# ESP_LED_CUBE.net
KiCad netlist of a schematic drawn in EAGLE
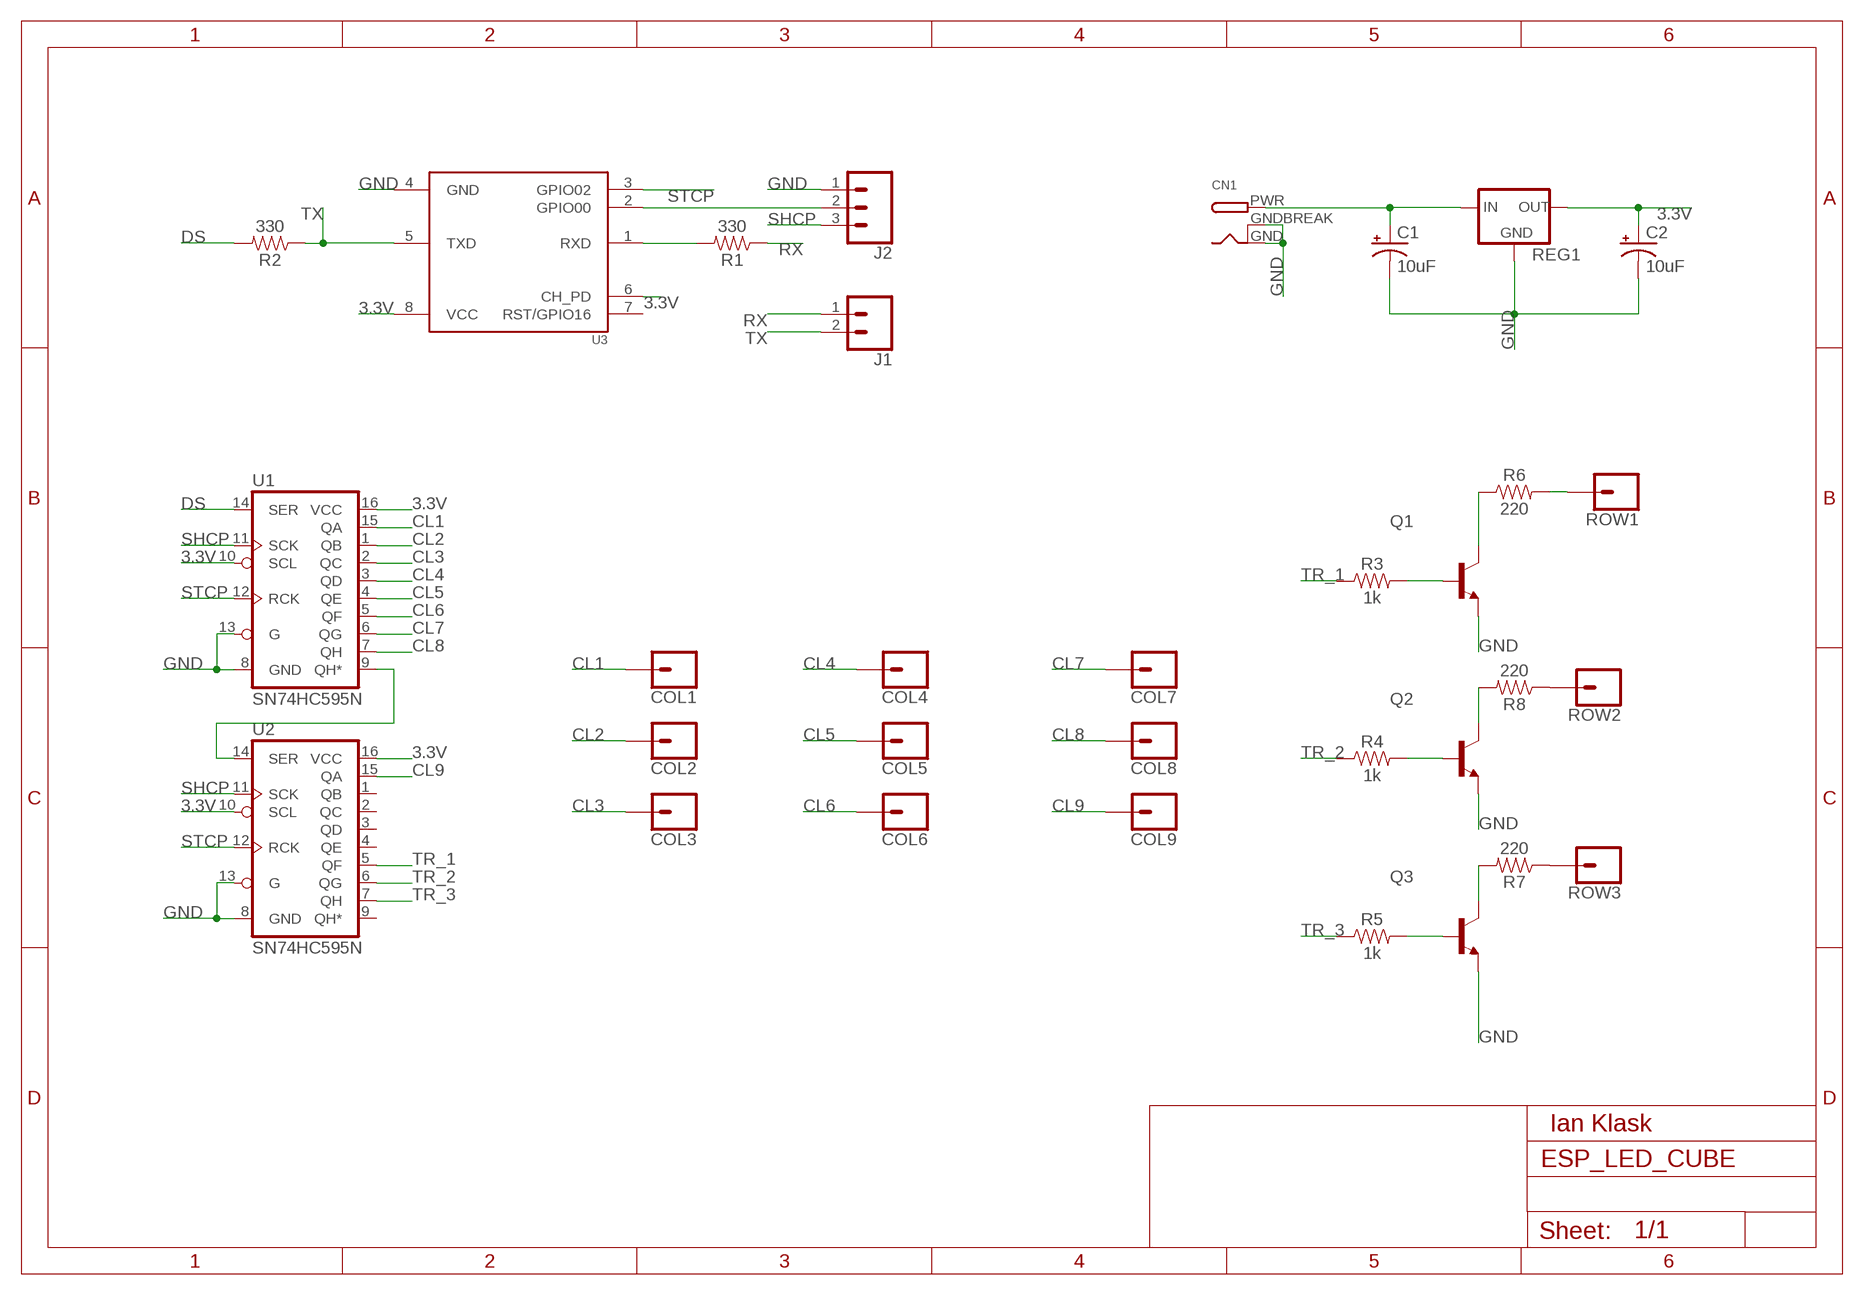
[diagram p0: schematic, sheet 1]

(export (version "E")
  (design (tool "Eeschema 10.0.6"))
  (components
    (comp (ref "C1")
      (value "10uF")
      (footprint "eagle-import:CPOL-RADIAL-2.5MM-5MM")
      (libsource (lib "eagle-import") (part "10UF-POLAR-RADIAL-2.5MM-25V-20%"))
    )
    (comp (ref "C2")
      (value "10uF")
      (footprint "eagle-import:CPOL-RADIAL-2.5MM-5MM")
      (libsource (lib "eagle-import") (part "10UF-POLAR-RADIAL-2.5MM-25V-20%"))
    )
    (comp (ref "CN1")
      (value "DCBARRELPTH")
      (footprint "eagle-import:DCJACK_2MM_PTH")
      (libsource (lib "eagle-import") (part "DCBARRELPTH"))
    )
    (comp (ref "COL1")
      (value "CONN_01")
      (footprint "eagle-import:1X01")
      (libsource (lib "eagle-import") (part "CONN_01"))
    )
    (comp (ref "COL2")
      (value "CONN_01")
      (footprint "eagle-import:1X01")
      (libsource (lib "eagle-import") (part "CONN_01"))
    )
    (comp (ref "COL3")
      (value "CONN_01")
      (footprint "eagle-import:1X01")
      (libsource (lib "eagle-import") (part "CONN_01"))
    )
    (comp (ref "COL4")
      (value "CONN_01")
      (footprint "eagle-import:1X01")
      (libsource (lib "eagle-import") (part "CONN_01"))
    )
    (comp (ref "COL5")
      (value "CONN_01")
      (footprint "eagle-import:1X01")
      (libsource (lib "eagle-import") (part "CONN_01"))
    )
    (comp (ref "COL6")
      (value "CONN_01")
      (footprint "eagle-import:1X01")
      (libsource (lib "eagle-import") (part "CONN_01"))
    )
    (comp (ref "COL7")
      (value "CONN_01")
      (footprint "eagle-import:1X01")
      (libsource (lib "eagle-import") (part "CONN_01"))
    )
    (comp (ref "COL8")
      (value "CONN_01")
      (footprint "eagle-import:1X01")
      (libsource (lib "eagle-import") (part "CONN_01"))
    )
    (comp (ref "COL9")
      (value "CONN_01")
      (footprint "eagle-import:1X01")
      (libsource (lib "eagle-import") (part "CONN_01"))
    )
    (comp (ref "J1")
      (value "CONN_02")
      (footprint "eagle-import:1X02")
      (libsource (lib "eagle-import") (part "CONN_02"))
    )
    (comp (ref "J2")
      (value "CONN_03")
      (footprint "eagle-import:1X03")
      (libsource (lib "eagle-import") (part "CONN_03"))
    )
    (comp (ref "Q1")
      (value "2N3904")
      (footprint "eagle-import:TO92")
      (libsource (lib "eagle-import") (part "2N3904"))
    )
    (comp (ref "Q2")
      (value "2N3904")
      (footprint "eagle-import:TO92")
      (libsource (lib "eagle-import") (part "2N3904"))
    )
    (comp (ref "Q3")
      (value "2N3904")
      (footprint "eagle-import:TO92")
      (libsource (lib "eagle-import") (part "2N3904"))
    )
    (comp (ref "R1")
      (value "330")
      (footprint "eagle-import:AXIAL-0.3")
      (libsource (lib "eagle-import") (part "330OHM-HORIZ-1/10W-5%"))
    )
    (comp (ref "R2")
      (value "330")
      (footprint "eagle-import:AXIAL-0.3")
      (libsource (lib "eagle-import") (part "330OHM-HORIZ-1/10W-5%"))
    )
    (comp (ref "R3")
      (value "1k")
      (footprint "eagle-import:AXIAL-0.3")
      (libsource (lib "eagle-import") (part "1KOHM-HORIZ-1/4W-1%"))
    )
    (comp (ref "R4")
      (value "1k")
      (footprint "eagle-import:AXIAL-0.3")
      (libsource (lib "eagle-import") (part "1KOHM-HORIZ-1/4W-1%"))
    )
    (comp (ref "R5")
      (value "1k")
      (footprint "eagle-import:AXIAL-0.3")
      (libsource (lib "eagle-import") (part "1KOHM-HORIZ-1/4W-1%"))
    )
    (comp (ref "R6")
      (value "220")
      (footprint "eagle-import:AXIAL-0.3")
      (libsource (lib "eagle-import") (part "330OHM-HORIZ-1/10W-5%"))
    )
    (comp (ref "R7")
      (value "220")
      (footprint "eagle-import:AXIAL-0.3")
      (libsource (lib "eagle-import") (part "330OHM-HORIZ-1/10W-5%"))
    )
    (comp (ref "R8")
      (value "220")
      (footprint "eagle-import:AXIAL-0.3")
      (libsource (lib "eagle-import") (part "330OHM-HORIZ-1/10W-5%"))
    )
    (comp (ref "REG1")
      (value "V_REG_LD1117VXX")
      (footprint "eagle-import:78XXL")
      (libsource (lib "eagle-import") (part "V_REG_LD1117VXX"))
    )
    (comp (ref "ROW1")
      (value "CONN_01")
      (footprint "eagle-import:1X01")
      (libsource (lib "eagle-import") (part "CONN_01"))
    )
    (comp (ref "ROW2")
      (value "CONN_01")
      (footprint "eagle-import:1X01")
      (libsource (lib "eagle-import") (part "CONN_01"))
    )
    (comp (ref "ROW3")
      (value "CONN_01")
      (footprint "eagle-import:1X01")
      (libsource (lib "eagle-import") (part "CONN_01"))
    )
    (comp (ref "U1")
      (value "SN74HC595N")
      (footprint "eagle-import:DIP16")
      (libsource (lib "eagle-import") (part "74595NHC"))
    )
    (comp (ref "U2")
      (value "SN74HC595N")
      (footprint "eagle-import:DIP16")
      (libsource (lib "eagle-import") (part "74595NHC"))
    )
    (comp (ref "U3")
      (value "ESP8266-01/ESP-01")
      (footprint "eagle-import:XCVR_ESP8266-01_ESP-01")
      (libsource (lib "eagle-import") (part "ESP8266-01/ESP-01"))
    )
  )
  (nets
    (net (code "1") (name "/3.3V") (class "Default")
      (node (ref "C2") (pin "1") (pinfunction "+_1") (pintype "passive"))
      (node (ref "REG1") (pin "GND") (pinfunction "OUT_GND") (pintype "passive"))
      (node (ref "U1") (pin "10") (pinfunction "SCL_10") (pintype "input"))
      (node (ref "U1") (pin "16") (pinfunction "VCC_16") (pintype "power_in"))
      (node (ref "U2") (pin "10") (pinfunction "SCL_10") (pintype "input"))
      (node (ref "U2") (pin "16") (pinfunction "VCC_16") (pintype "power_in"))
      (node (ref "U3") (pin "6") (pinfunction "CH_PD_6") (pintype "input"))
      (node (ref "U3") (pin "8") (pinfunction "VCC_8") (pintype "power_in"))
    )
    (net (code "2") (name "/CL1") (class "Default")
      (node (ref "COL1") (pin "1") (pinfunction "1_1") (pintype "passive"))
      (node (ref "U1") (pin "15") (pinfunction "QA_15") (pintype "tri_state"))
    )
    (net (code "3") (name "/CL2") (class "Default")
      (node (ref "COL2") (pin "1") (pinfunction "1_1") (pintype "passive"))
      (node (ref "U1") (pin "1") (pinfunction "QB_1") (pintype "tri_state"))
    )
    (net (code "4") (name "/CL3") (class "Default")
      (node (ref "COL3") (pin "1") (pinfunction "1_1") (pintype "passive"))
      (node (ref "U1") (pin "2") (pinfunction "QC_2") (pintype "tri_state"))
    )
    (net (code "5") (name "/CL4") (class "Default")
      (node (ref "COL4") (pin "1") (pinfunction "1_1") (pintype "passive"))
      (node (ref "U1") (pin "3") (pinfunction "QD_3") (pintype "tri_state"))
    )
    (net (code "6") (name "/CL5") (class "Default")
      (node (ref "COL5") (pin "1") (pinfunction "1_1") (pintype "passive"))
      (node (ref "U1") (pin "4") (pinfunction "QE_4") (pintype "tri_state"))
    )
    (net (code "7") (name "/CL6") (class "Default")
      (node (ref "COL6") (pin "1") (pinfunction "1_1") (pintype "passive"))
      (node (ref "U1") (pin "5") (pinfunction "QF_5") (pintype "tri_state"))
    )
    (net (code "8") (name "/CL7") (class "Default")
      (node (ref "COL7") (pin "1") (pinfunction "1_1") (pintype "passive"))
      (node (ref "U1") (pin "6") (pinfunction "QG_6") (pintype "tri_state"))
    )
    (net (code "9") (name "/CL8") (class "Default")
      (node (ref "COL8") (pin "1") (pinfunction "1_1") (pintype "passive"))
      (node (ref "U1") (pin "7") (pinfunction "QH_7") (pintype "tri_state"))
    )
    (net (code "10") (name "/CL9") (class "Default")
      (node (ref "COL9") (pin "1") (pinfunction "1_1") (pintype "passive"))
      (node (ref "U2") (pin "15") (pinfunction "QA_15") (pintype "tri_state"))
    )
    (net (code "11") (name "/DS") (class "Default")
      (node (ref "R2") (pin "P$2") (pinfunction "2_P$2") (pintype "passive"))
      (node (ref "U1") (pin "14") (pinfunction "SER_14") (pintype "input"))
    )
    (net (code "12") (name "/GND") (class "Default")
      (node (ref "C1") (pin "2") (pinfunction "-_2") (pintype "passive"))
      (node (ref "C2") (pin "2") (pinfunction "-_2") (pintype "passive"))
      (node (ref "CN1") (pin "GND") (pinfunction "GND_GND") (pintype "power_in"))
      (node (ref "CN1") (pin "GNDBREAK") (pinfunction "GNDBREAK_GNDBREAK") (pintype "power_in"))
      (node (ref "J2") (pin "1") (pinfunction "1_1") (pintype "passive"))
      (node (ref "Q1") (pin "3") (pinfunction "E_3") (pintype "passive"))
      (node (ref "Q2") (pin "3") (pinfunction "E_3") (pintype "passive"))
      (node (ref "Q3") (pin "3") (pinfunction "E_3") (pintype "passive"))
      (node (ref "REG1") (pin "IN") (pinfunction "GND_IN") (pintype "input"))
      (node (ref "U1") (pin "13") (pinfunction "G_13") (pintype "input"))
      (node (ref "U1") (pin "8") (pinfunction "GND_8") (pintype "power_in"))
      (node (ref "U2") (pin "13") (pinfunction "G_13") (pintype "input"))
      (node (ref "U2") (pin "8") (pinfunction "GND_8") (pintype "power_in"))
      (node (ref "U3") (pin "4") (pinfunction "GND_4") (pintype "power_in"))
    )
    (net (code "13") (name "/RX") (class "Default")
      (node (ref "J1") (pin "1") (pinfunction "1_1") (pintype "passive"))
      (node (ref "R1") (pin "P$1") (pinfunction "1_P$1") (pintype "passive"))
    )
    (net (code "14") (name "/SHCP") (class "Default")
      (node (ref "J2") (pin "3") (pinfunction "3_3") (pintype "passive"))
      (node (ref "U1") (pin "11") (pinfunction "SCK_11") (pintype "input"))
      (node (ref "U2") (pin "11") (pinfunction "SCK_11") (pintype "input"))
    )
    (net (code "15") (name "/STCP") (class "Default")
      (node (ref "U1") (pin "12") (pinfunction "RCK_12") (pintype "input"))
      (node (ref "U2") (pin "12") (pinfunction "RCK_12") (pintype "input"))
      (node (ref "U3") (pin "3") (pinfunction "GPIO02_3") (pintype "bidirectional"))
    )
    (net (code "16") (name "/TR_1") (class "Default")
      (node (ref "R3") (pin "P$1") (pinfunction "1_P$1") (pintype "passive"))
      (node (ref "U2") (pin "5") (pinfunction "QF_5") (pintype "tri_state"))
    )
    (net (code "17") (name "/TR_2") (class "Default")
      (node (ref "R4") (pin "P$1") (pinfunction "1_P$1") (pintype "passive"))
      (node (ref "U2") (pin "6") (pinfunction "QG_6") (pintype "tri_state"))
    )
    (net (code "18") (name "/TR_3") (class "Default")
      (node (ref "R5") (pin "P$1") (pinfunction "1_P$1") (pintype "passive"))
      (node (ref "U2") (pin "7") (pinfunction "QH_7") (pintype "tri_state"))
    )
    (net (code "19") (name "/TX") (class "Default")
      (node (ref "J1") (pin "2") (pinfunction "2_2") (pintype "passive"))
      (node (ref "R2") (pin "P$1") (pinfunction "1_P$1") (pintype "passive"))
      (node (ref "U3") (pin "5") (pinfunction "TXD_5") (pintype "output"))
    )
    (net (code "20") (name "Net-(C1-+)") (class "Default")
      (node (ref "C1") (pin "1") (pinfunction "+_1") (pintype "passive"))
      (node (ref "CN1") (pin "PWR") (pinfunction "PWR_PWR") (pintype "power_in"))
      (node (ref "REG1") (pin "OUT") (pinfunction "IN_OUT") (pintype "input"))
    )
    (net (code "21") (name "Net-(Q1-B)") (class "Default")
      (node (ref "Q1") (pin "2") (pinfunction "B_2") (pintype "passive"))
      (node (ref "R3") (pin "P$2") (pinfunction "2_P$2") (pintype "passive"))
    )
    (net (code "22") (name "Net-(Q1-C)") (class "Default")
      (node (ref "Q1") (pin "1") (pinfunction "C_1") (pintype "passive"))
      (node (ref "R6") (pin "P$1") (pinfunction "1_P$1") (pintype "passive"))
    )
    (net (code "23") (name "Net-(Q2-B)") (class "Default")
      (node (ref "Q2") (pin "2") (pinfunction "B_2") (pintype "passive"))
      (node (ref "R4") (pin "P$2") (pinfunction "2_P$2") (pintype "passive"))
    )
    (net (code "24") (name "Net-(Q2-C)") (class "Default")
      (node (ref "Q2") (pin "1") (pinfunction "C_1") (pintype "passive"))
      (node (ref "R8") (pin "P$2") (pinfunction "2_P$2") (pintype "passive"))
    )
    (net (code "25") (name "Net-(Q3-B)") (class "Default")
      (node (ref "Q3") (pin "2") (pinfunction "B_2") (pintype "passive"))
      (node (ref "R5") (pin "P$2") (pinfunction "2_P$2") (pintype "passive"))
    )
    (net (code "26") (name "Net-(Q3-C)") (class "Default")
      (node (ref "Q3") (pin "1") (pinfunction "C_1") (pintype "passive"))
      (node (ref "R7") (pin "P$2") (pinfunction "2_P$2") (pintype "passive"))
    )
    (net (code "27") (name "Net-(R1-2)") (class "Default")
      (node (ref "R1") (pin "P$2") (pinfunction "2_P$2") (pintype "passive"))
      (node (ref "U3") (pin "1") (pinfunction "RXD_1") (pintype "input"))
    )
    (net (code "28") (name "Net-(R6-2)") (class "Default")
      (node (ref "R6") (pin "P$2") (pinfunction "2_P$2") (pintype "passive"))
      (node (ref "ROW1") (pin "1") (pinfunction "1_1") (pintype "passive"))
    )
    (net (code "29") (name "Net-(R7-1)") (class "Default")
      (node (ref "R7") (pin "P$1") (pinfunction "1_P$1") (pintype "passive"))
      (node (ref "ROW3") (pin "1") (pinfunction "1_1") (pintype "passive"))
    )
    (net (code "30") (name "Net-(R8-1)") (class "Default")
      (node (ref "R8") (pin "P$1") (pinfunction "1_P$1") (pintype "passive"))
      (node (ref "ROW2") (pin "1") (pinfunction "1_1") (pintype "passive"))
    )
    (net (code "31") (name "Net-(U1-QH*)") (class "Default")
      (node (ref "U1") (pin "9") (pinfunction "QH*_9") (pintype "tri_state"))
      (node (ref "U2") (pin "14") (pinfunction "SER_14") (pintype "input"))
    )
    (net (code "32") (name "Net-(U3-GPIO00)") (class "Default")
      (node (ref "J2") (pin "2") (pinfunction "2_2") (pintype "passive"))
      (node (ref "U3") (pin "2") (pinfunction "GPIO00_2") (pintype "bidirectional"))
    )
    (net (code "33") (name "unconnected-(U2-QB-Pad1)") (class "Default")
      (node (ref "U2") (pin "1") (pinfunction "QB_1") (pintype "tri_state"))
    )
    (net (code "34") (name "unconnected-(U2-QC-Pad2)") (class "Default")
      (node (ref "U2") (pin "2") (pinfunction "QC_2") (pintype "tri_state"))
    )
    (net (code "35") (name "unconnected-(U2-QD-Pad3)") (class "Default")
      (node (ref "U2") (pin "3") (pinfunction "QD_3") (pintype "tri_state"))
    )
    (net (code "36") (name "unconnected-(U2-QE-Pad4)") (class "Default")
      (node (ref "U2") (pin "4") (pinfunction "QE_4") (pintype "tri_state"))
    )
    (net (code "37") (name "unconnected-(U2-QH*-Pad9)") (class "Default")
      (node (ref "U2") (pin "9") (pinfunction "QH*_9") (pintype "tri_state"))
    )
    (net (code "38") (name "unconnected-(U3-RST{slash}GPIO16-Pad7)") (class "Default")
      (node (ref "U3") (pin "7") (pinfunction "RST/GPIO16_7") (pintype "input"))
    )
  )
)
